# Power_Board_V2.net
KiCad netlist of a schematic drawn in EAGLE
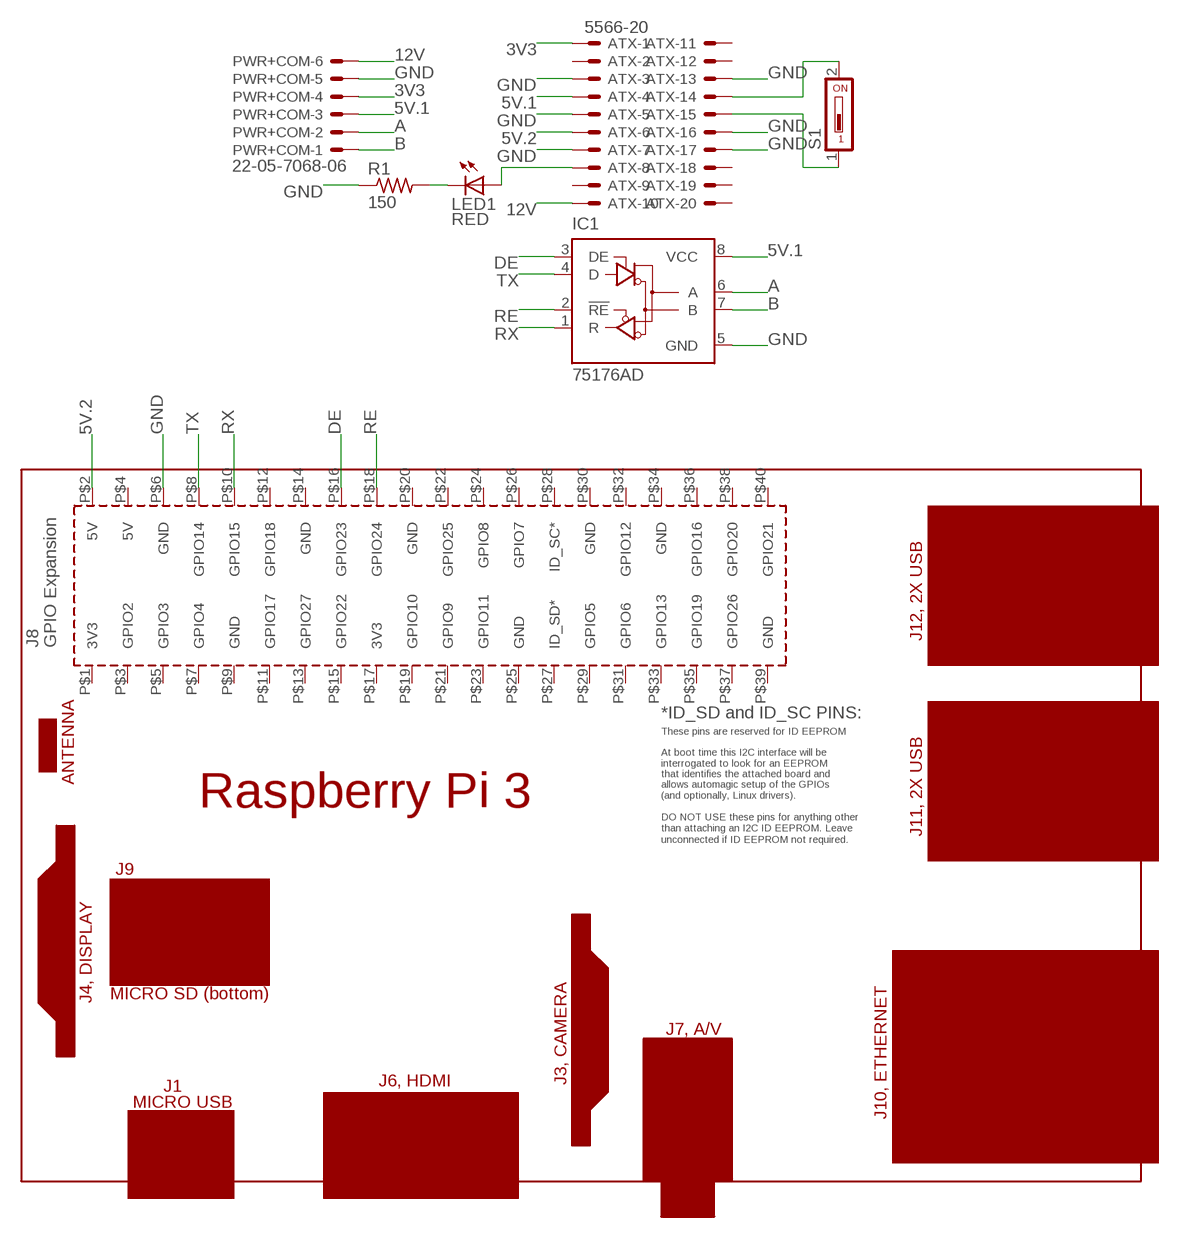
[diagram p0: schematic, sheet 1]

(export (version "E")
  (design (tool "Eeschema 10.0.6"))
  (components
    (comp (ref "ATX")
      (value "5566-20")
      (footprint "eagle-import:5566-20")
      (libsource (lib "eagle-import") (part "5566-20"))
    )
    (comp (ref "IC1")
      (value "75176AD")
      (footprint "eagle-import:D_R-PDSO-G8")
      (libsource (lib "eagle-import") (part "75176AD"))
    )
    (comp (ref "LED1")
      (value "RED")
      (footprint "eagle-import:CHIPLED_1206")
      (libsource (lib "eagle-import") (part "LEDCHIPLED_1206"))
    )
    (comp (ref "PCB1")
      (value "RPI3")
      (footprint "eagle-import:RPI3")
      (libsource (lib "eagle-import") (part "RPI3"))
    )
    (comp (ref "PWR+COM")
      (value "22-05-7068-06")
      (footprint "eagle-import:7395-06")
      (libsource (lib "eagle-import") (part "22-?-0605-7068"))
    )
    (comp (ref "R1")
      (value "150")
      (footprint "eagle-import:R0805")
      (libsource (lib "eagle-import") (part "R-US_R0805"))
    )
    (comp (ref "S1")
      (value "SD4-01")
      (footprint "eagle-import:SD4-01")
      (libsource (lib "eagle-import") (part "SD4-01"))
    )
  )
  (nets
    (net (code "1") (name "/3V3") (class "Default")
      (node (ref "ATX") (pin "1") (pinfunction "S_1") (pintype "passive"))
      (node (ref "PWR+COM") (pin "4") (pinfunction "S_4") (pintype "passive"))
    )
    (net (code "2") (name "/5V.1") (class "Default")
      (node (ref "ATX") (pin "4") (pinfunction "S_4") (pintype "passive"))
      (node (ref "IC1") (pin "8") (pinfunction "VCC_8") (pintype "power_in"))
      (node (ref "PWR+COM") (pin "3") (pinfunction "S_3") (pintype "passive"))
    )
    (net (code "3") (name "/5V.2") (class "Default")
      (node (ref "ATX") (pin "6") (pinfunction "S_6") (pintype "passive"))
      (node (ref "PCB1") (pin "P$2") (pinfunction "5V_P$2") (pintype "bidirectional"))
    )
    (net (code "4") (name "/12V") (class "Default")
      (node (ref "ATX") (pin "10") (pinfunction "S_10") (pintype "passive"))
      (node (ref "PWR+COM") (pin "6") (pinfunction "S_6") (pintype "passive"))
    )
    (net (code "5") (name "/A") (class "Default")
      (node (ref "IC1") (pin "6") (pinfunction "A_6") (pintype "output"))
      (node (ref "PWR+COM") (pin "2") (pinfunction "S_2") (pintype "passive"))
    )
    (net (code "6") (name "/B") (class "Default")
      (node (ref "IC1") (pin "7") (pinfunction "B_7") (pintype "output"))
      (node (ref "PWR+COM") (pin "1") (pinfunction "S_1") (pintype "passive"))
    )
    (net (code "7") (name "/DE") (class "Default")
      (node (ref "IC1") (pin "3") (pinfunction "DE_3") (pintype "input"))
      (node (ref "PCB1") (pin "P$16") (pinfunction "GPIO23_P$16") (pintype "bidirectional"))
    )
    (net (code "8") (name "/GND") (class "Default")
      (node (ref "ATX") (pin "13") (pinfunction "S_13") (pintype "passive"))
      (node (ref "ATX") (pin "16") (pinfunction "S_16") (pintype "passive"))
      (node (ref "ATX") (pin "17") (pinfunction "S_17") (pintype "passive"))
      (node (ref "ATX") (pin "3") (pinfunction "S_3") (pintype "passive"))
      (node (ref "ATX") (pin "5") (pinfunction "S_5") (pintype "passive"))
      (node (ref "ATX") (pin "7") (pinfunction "S_7") (pintype "passive"))
      (node (ref "IC1") (pin "5") (pinfunction "GND_5") (pintype "power_in"))
      (node (ref "PCB1") (pin "P$6") (pinfunction "GND_P$6") (pintype "bidirectional"))
      (node (ref "PWR+COM") (pin "5") (pinfunction "S_5") (pintype "passive"))
      (node (ref "R1") (pin "1") (pinfunction "1_1") (pintype "passive"))
    )
    (net (code "9") (name "/RE") (class "Default")
      (node (ref "IC1") (pin "2") (pinfunction "~{RE}_2") (pintype "input"))
      (node (ref "PCB1") (pin "P$18") (pinfunction "GPIO24_P$18") (pintype "bidirectional"))
    )
    (net (code "10") (name "/RX") (class "Default")
      (node (ref "IC1") (pin "1") (pinfunction "R_1") (pintype "input"))
      (node (ref "PCB1") (pin "P$10") (pinfunction "GPIO15_P$10") (pintype "bidirectional"))
    )
    (net (code "11") (name "/TX") (class "Default")
      (node (ref "IC1") (pin "4") (pinfunction "D_4") (pintype "input"))
      (node (ref "PCB1") (pin "P$8") (pinfunction "GPIO14_P$8") (pintype "bidirectional"))
    )
    (net (code "12") (name "Net-(ATXF-S)") (class "Default")
      (node (ref "ATX") (pin "14") (pinfunction "S_14") (pintype "passive"))
      (node (ref "S1") (pin "2") (pinfunction "2_2") (pintype "passive"))
    )
    (net (code "13") (name "Net-(ATXG-S)") (class "Default")
      (node (ref "ATX") (pin "15") (pinfunction "S_15") (pintype "passive"))
      (node (ref "S1") (pin "1") (pinfunction "1_1") (pintype "passive"))
    )
    (net (code "14") (name "Net-(ATXS-S)") (class "Default")
      (node (ref "ATX") (pin "8") (pinfunction "S_8") (pintype "passive"))
      (node (ref "LED1") (pin "A") (pinfunction "A_A") (pintype "passive"))
    )
    (net (code "15") (name "Net-(LED1-PadC)") (class "Default")
      (node (ref "LED1") (pin "C") (pinfunction "C_C") (pintype "passive"))
      (node (ref "R1") (pin "2") (pinfunction "2_2") (pintype "passive"))
    )
    (net (code "16") (name "unconnected-(ATXC-S-Pad11)") (class "Default")
      (node (ref "ATX") (pin "11") (pinfunction "S_11") (pintype "passive"))
    )
    (net (code "17") (name "unconnected-(ATXD-S-Pad12)") (class "Default")
      (node (ref "ATX") (pin "12") (pinfunction "S_12") (pintype "passive"))
    )
    (net (code "18") (name "unconnected-(ATXJ-S-Pad18)") (class "Default")
      (node (ref "ATX") (pin "18") (pinfunction "S_18") (pintype "passive"))
    )
    (net (code "19") (name "unconnected-(ATXK-S-Pad19)") (class "Default")
      (node (ref "ATX") (pin "19") (pinfunction "S_19") (pintype "passive"))
    )
    (net (code "20") (name "unconnected-(ATXL-S-Pad2)") (class "Default")
      (node (ref "ATX") (pin "2") (pinfunction "S_2") (pintype "passive"))
    )
    (net (code "21") (name "unconnected-(ATXM-S-Pad20)") (class "Default")
      (node (ref "ATX") (pin "20") (pinfunction "S_20") (pintype "passive"))
    )
    (net (code "22") (name "unconnected-(ATXT-S-Pad9)") (class "Default")
      (node (ref "ATX") (pin "9") (pinfunction "S_9") (pintype "passive"))
    )
    (net (code "23") (name "unconnected-(PCB1-3V3-PadP$1)") (class "Default")
      (node (ref "PCB1") (pin "P$1") (pinfunction "3V3_P$1") (pintype "bidirectional"))
    )
    (net (code "24") (name "unconnected-(PCB1-3V3-PadP$17)") (class "Default")
      (node (ref "PCB1") (pin "P$17") (pinfunction "3V3_P$17") (pintype "bidirectional"))
    )
    (net (code "25") (name "unconnected-(PCB1-5V-PadP$4)") (class "Default")
      (node (ref "PCB1") (pin "P$4") (pinfunction "5V_P$4") (pintype "bidirectional"))
    )
    (net (code "26") (name "unconnected-(PCB1-GND-PadP$9)") (class "Default")
      (node (ref "PCB1") (pin "P$9") (pinfunction "GND_P$9") (pintype "bidirectional"))
    )
    (net (code "27") (name "unconnected-(PCB1-GND-PadP$14)") (class "Default")
      (node (ref "PCB1") (pin "P$14") (pinfunction "GND_P$14") (pintype "bidirectional"))
    )
    (net (code "28") (name "unconnected-(PCB1-GND-PadP$20)") (class "Default")
      (node (ref "PCB1") (pin "P$20") (pinfunction "GND_P$20") (pintype "bidirectional"))
    )
    (net (code "29") (name "unconnected-(PCB1-GND-PadP$25)") (class "Default")
      (node (ref "PCB1") (pin "P$25") (pinfunction "GND_P$25") (pintype "bidirectional"))
    )
    (net (code "30") (name "unconnected-(PCB1-GND-PadP$30)") (class "Default")
      (node (ref "PCB1") (pin "P$30") (pinfunction "GND_P$30") (pintype "bidirectional"))
    )
    (net (code "31") (name "unconnected-(PCB1-GND-PadP$34)") (class "Default")
      (node (ref "PCB1") (pin "P$34") (pinfunction "GND_P$34") (pintype "bidirectional"))
    )
    (net (code "32") (name "unconnected-(PCB1-GND-PadP$39)") (class "Default")
      (node (ref "PCB1") (pin "P$39") (pinfunction "GND_P$39") (pintype "bidirectional"))
    )
    (net (code "33") (name "unconnected-(PCB1-GPIO2-PadP$3)") (class "Default")
      (node (ref "PCB1") (pin "P$3") (pinfunction "GPIO2_P$3") (pintype "bidirectional"))
    )
    (net (code "34") (name "unconnected-(PCB1-GPIO3-PadP$5)") (class "Default")
      (node (ref "PCB1") (pin "P$5") (pinfunction "GPIO3_P$5") (pintype "bidirectional"))
    )
    (net (code "35") (name "unconnected-(PCB1-GPIO4-PadP$7)") (class "Default")
      (node (ref "PCB1") (pin "P$7") (pinfunction "GPIO4_P$7") (pintype "bidirectional"))
    )
    (net (code "36") (name "unconnected-(PCB1-GPIO5-PadP$29)") (class "Default")
      (node (ref "PCB1") (pin "P$29") (pinfunction "GPIO5_P$29") (pintype "bidirectional"))
    )
    (net (code "37") (name "unconnected-(PCB1-GPIO6-PadP$31)") (class "Default")
      (node (ref "PCB1") (pin "P$31") (pinfunction "GPIO6_P$31") (pintype "bidirectional"))
    )
    (net (code "38") (name "unconnected-(PCB1-GPIO7-PadP$26)") (class "Default")
      (node (ref "PCB1") (pin "P$26") (pinfunction "GPIO7_P$26") (pintype "bidirectional"))
    )
    (net (code "39") (name "unconnected-(PCB1-GPIO8-PadP$24)") (class "Default")
      (node (ref "PCB1") (pin "P$24") (pinfunction "GPIO8_P$24") (pintype "bidirectional"))
    )
    (net (code "40") (name "unconnected-(PCB1-GPIO9-PadP$21)") (class "Default")
      (node (ref "PCB1") (pin "P$21") (pinfunction "GPIO9_P$21") (pintype "bidirectional"))
    )
    (net (code "41") (name "unconnected-(PCB1-GPIO10-PadP$19)") (class "Default")
      (node (ref "PCB1") (pin "P$19") (pinfunction "GPIO10_P$19") (pintype "bidirectional"))
    )
    (net (code "42") (name "unconnected-(PCB1-GPIO11-PadP$23)") (class "Default")
      (node (ref "PCB1") (pin "P$23") (pinfunction "GPIO11_P$23") (pintype "bidirectional"))
    )
    (net (code "43") (name "unconnected-(PCB1-GPIO12-PadP$32)") (class "Default")
      (node (ref "PCB1") (pin "P$32") (pinfunction "GPIO12_P$32") (pintype "bidirectional"))
    )
    (net (code "44") (name "unconnected-(PCB1-GPIO13-PadP$33)") (class "Default")
      (node (ref "PCB1") (pin "P$33") (pinfunction "GPIO13_P$33") (pintype "bidirectional"))
    )
    (net (code "45") (name "unconnected-(PCB1-GPIO16-PadP$36)") (class "Default")
      (node (ref "PCB1") (pin "P$36") (pinfunction "GPIO16_P$36") (pintype "bidirectional"))
    )
    (net (code "46") (name "unconnected-(PCB1-GPIO17-PadP$11)") (class "Default")
      (node (ref "PCB1") (pin "P$11") (pinfunction "GPIO17_P$11") (pintype "bidirectional"))
    )
    (net (code "47") (name "unconnected-(PCB1-GPIO18-PadP$12)") (class "Default")
      (node (ref "PCB1") (pin "P$12") (pinfunction "GPIO18_P$12") (pintype "bidirectional"))
    )
    (net (code "48") (name "unconnected-(PCB1-GPIO19-PadP$35)") (class "Default")
      (node (ref "PCB1") (pin "P$35") (pinfunction "GPIO19_P$35") (pintype "bidirectional"))
    )
    (net (code "49") (name "unconnected-(PCB1-GPIO20-PadP$38)") (class "Default")
      (node (ref "PCB1") (pin "P$38") (pinfunction "GPIO20_P$38") (pintype "bidirectional"))
    )
    (net (code "50") (name "unconnected-(PCB1-GPIO21-PadP$40)") (class "Default")
      (node (ref "PCB1") (pin "P$40") (pinfunction "GPIO21_P$40") (pintype "bidirectional"))
    )
    (net (code "51") (name "unconnected-(PCB1-GPIO22-PadP$15)") (class "Default")
      (node (ref "PCB1") (pin "P$15") (pinfunction "GPIO22_P$15") (pintype "bidirectional"))
    )
    (net (code "52") (name "unconnected-(PCB1-GPIO25-PadP$22)") (class "Default")
      (node (ref "PCB1") (pin "P$22") (pinfunction "GPIO25_P$22") (pintype "bidirectional"))
    )
    (net (code "53") (name "unconnected-(PCB1-GPIO26-PadP$37)") (class "Default")
      (node (ref "PCB1") (pin "P$37") (pinfunction "GPIO26_P$37") (pintype "bidirectional"))
    )
    (net (code "54") (name "unconnected-(PCB1-GPIO27-PadP$13)") (class "Default")
      (node (ref "PCB1") (pin "P$13") (pinfunction "GPIO27_P$13") (pintype "bidirectional"))
    )
    (net (code "55") (name "unconnected-(PCB1-ID_SC*-PadP$28)") (class "Default")
      (node (ref "PCB1") (pin "P$28") (pinfunction "ID_SC*_P$28") (pintype "bidirectional"))
    )
    (net (code "56") (name "unconnected-(PCB1-ID_SD*-PadP$27)") (class "Default")
      (node (ref "PCB1") (pin "P$27") (pinfunction "ID_SD*_P$27") (pintype "bidirectional"))
    )
  )
)
